# BPF_LNA.net
KiCad netlist of a schematic drawn in Altium Designer
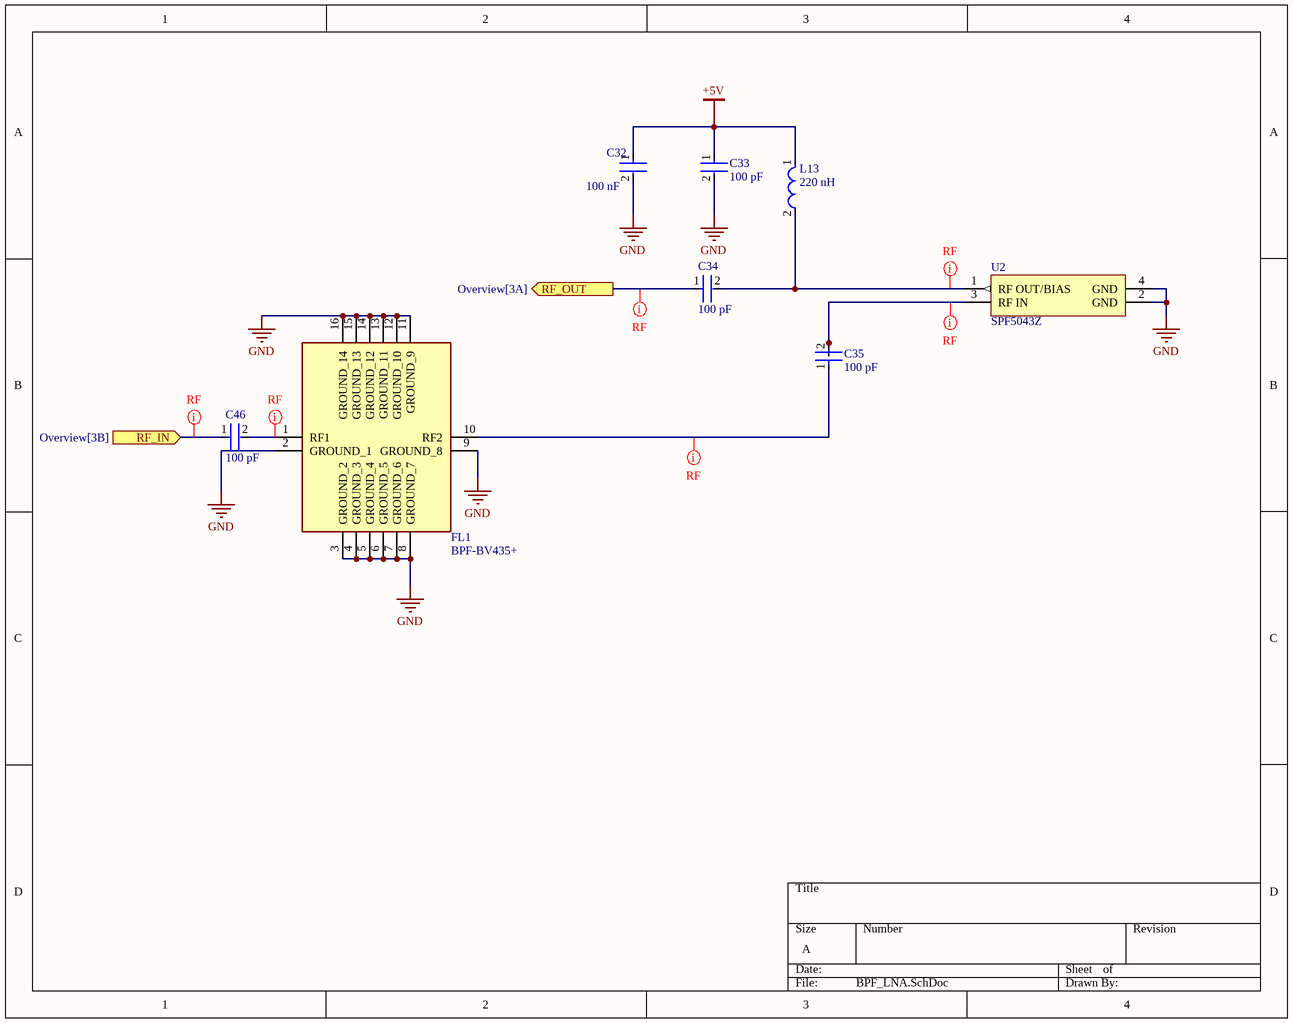
[diagram p0: BPF_LNA.SchDoc]

(export (version "E")
  (design (tool "Eeschema 10.0.6"))
  (components
    (comp (ref "C32")
      (value "100 nF")
      (footprint "FP-GCM155-0_05-IPC_C")
      (description "Ceramic Capacitor for Automotive 100nF ±10% 16VDC X7R 0402 Paper T/R Name: GCM155R71C104KA55D")
      (fields (field (name "VOLTAGE") "16V") (field (name "TOLERANCE") "10%"))
      (libsource (lib "Altium Content Vault") (part "02cd4be3c70576c341d710602a673aa"))
    )
    (comp (ref "C33")
      (value "100 pF")
      (footprint "FP-GQM187-0_15-MFG")
      (description "Ceramic Capacitor 100pF ±5% 250VDC C0G 0603 Paper T/R Name: GQM1875C2E101JB12D")
      (fields (field (name "TOLERANCE") "5%"))
      (libsource (lib "Altium Content Vault") (part "02cd4be3c70576c341d710602a673aa"))
    )
    (comp (ref "C34")
      (value "100 pF")
      (footprint "FP-GQM187-0_15-MFG")
      (description "Ceramic Capacitor 100pF ±5% 250VDC C0G 0603 Paper T/R Name: GQM1875C2E101JB12D")
      (fields (field (name "TOLERANCE") "5%"))
      (libsource (lib "Altium Content Vault") (part "02cd4be3c70576c341d710602a673aa"))
    )
    (comp (ref "C35")
      (value "100 pF")
      (footprint "FP-GQM187-0_15-MFG")
      (description "Ceramic Capacitor 100pF ±5% 250VDC C0G 0603 Paper T/R Name: GQM1875C2E101JB12D")
      (fields (field (name "TOLERANCE") "5%"))
      (libsource (lib "Altium Content Vault") (part "02cd4be3c70576c341d710602a673aa"))
    )
    (comp (ref "C46")
      (value "100 pF")
      (footprint "FP-GQM187-0_15-MFG")
      (description "Ceramic Capacitor 100pF ±5% 250VDC C0G 0603 Paper T/R Name: GQM1875C2E101JB12D")
      (fields (field (name "TOLERANCE") "5%"))
      (libsource (lib "Altium Content Vault") (part "02cd4be3c70576c341d710602a673aa"))
    )
    (comp (ref "FL1")
      (value "BPF-BV435+")
      (footprint "SamacSys:BPFBV435")
      (description "Filter")
      (libsource (lib "*") (part "BPF-BV435+"))
    )
    (comp (ref "L13")
      (value "220 nH")
      (footprint "FP-LQW18AN_80-MFG")
      (description "Wire Wound RF Inductor for Automotive 220nH ±5% 280mA 2.08Ω 0603 (1608) Name: LQW18ANR22J8ZD")
      (libsource (lib "Altium Content Vault") (part "725321dda6339637d4d059423bc1c3c"))
    )
    (comp (ref "U2")
      (value "SPF5043Z")
      (footprint "RFMD-SOT343-4_M")
      (description "AMP, RF, LNA, 50-4000MHZ, SOT343")
      (fields (field (name "MANUFACTURER") "RF Micro Devices"))
      (libsource (lib "Altium Content Vault") (part "RFMD-SPF5043Z-SOT343-4"))
    )
  )
  (nets
    (net (code "1") (name "+5V") (class "Default")
      (node (ref "C32") (pin "1") (pinfunction "1_1") (pintype "passive"))
      (node (ref "C33") (pin "1") (pinfunction "1_1") (pintype "passive"))
      (node (ref "L13") (pin "1") (pinfunction "1_1") (pintype "passive"))
    )
    (net (code "2") (name "/RF_IN") (class "Default")
      (node (ref "C46") (pin "1") (pinfunction "1_1") (pintype "passive"))
    )
    (net (code "3") (name "/RF_OUT") (class "Default")
      (node (ref "C34") (pin "1") (pinfunction "1_1") (pintype "passive"))
    )
    (net (code "4") (name "GND") (class "Default")
      (node (ref "C32") (pin "2") (pinfunction "2_2") (pintype "passive"))
      (node (ref "C33") (pin "2") (pinfunction "2_2") (pintype "passive"))
      (node (ref "FL1") (pin "11") (pinfunction "GROUND_9_11") (pintype "passive"))
      (node (ref "FL1") (pin "12") (pinfunction "GROUND_10_12") (pintype "passive"))
      (node (ref "FL1") (pin "13") (pinfunction "GROUND_11_13") (pintype "passive"))
      (node (ref "FL1") (pin "14") (pinfunction "GROUND_12_14") (pintype "passive"))
      (node (ref "FL1") (pin "15") (pinfunction "GROUND_13_15") (pintype "passive"))
      (node (ref "FL1") (pin "16") (pinfunction "GROUND_14_16") (pintype "passive"))
      (node (ref "FL1") (pin "2") (pinfunction "GROUND_1_2") (pintype "passive"))
      (node (ref "FL1") (pin "3") (pinfunction "GROUND_2_3") (pintype "passive"))
      (node (ref "FL1") (pin "4") (pinfunction "GROUND_3_4") (pintype "passive"))
      (node (ref "FL1") (pin "5") (pinfunction "GROUND_4_5") (pintype "passive"))
      (node (ref "FL1") (pin "6") (pinfunction "GROUND_5_6") (pintype "passive"))
      (node (ref "FL1") (pin "7") (pinfunction "GROUND_6_7") (pintype "passive"))
      (node (ref "FL1") (pin "8") (pinfunction "GROUND_7_8") (pintype "passive"))
      (node (ref "FL1") (pin "9") (pinfunction "GROUND_8_9") (pintype "passive"))
      (node (ref "U2") (pin "2") (pinfunction "GND_2") (pintype "power_in"))
      (node (ref "U2") (pin "4") (pinfunction "GND_4") (pintype "power_in"))
    )
    (net (code "5") (name "Net-(FL1-RF1)") (class "Default")
      (node (ref "C46") (pin "2") (pinfunction "2_2") (pintype "passive"))
      (node (ref "FL1") (pin "1") (pinfunction "RF1_1") (pintype "passive"))
    )
    (net (code "6") (name "Net-(FL1-RF2)") (class "Default")
      (node (ref "C35") (pin "1") (pinfunction "1_1") (pintype "passive"))
      (node (ref "FL1") (pin "10") (pinfunction "RF2_10") (pintype "passive"))
    )
    (net (code "7") (name "Net-(U2-RF_IN)") (class "Default")
      (node (ref "C35") (pin "2") (pinfunction "2_2") (pintype "passive"))
      (node (ref "U2") (pin "3") (pinfunction "RF_IN_3") (pintype "passive"))
    )
    (net (code "8") (name "Net-(U2-RF_OUT{slash}BIAS)") (class "Default")
      (node (ref "C34") (pin "2") (pinfunction "2_2") (pintype "passive"))
      (node (ref "L13") (pin "2") (pinfunction "2_2") (pintype "passive"))
      (node (ref "U2") (pin "1") (pinfunction "RF_OUT/BIAS_1") (pintype "output"))
    )
  )
)
